# atmega16-128.net
KiCad netlist of a schematic drawn in EAGLE
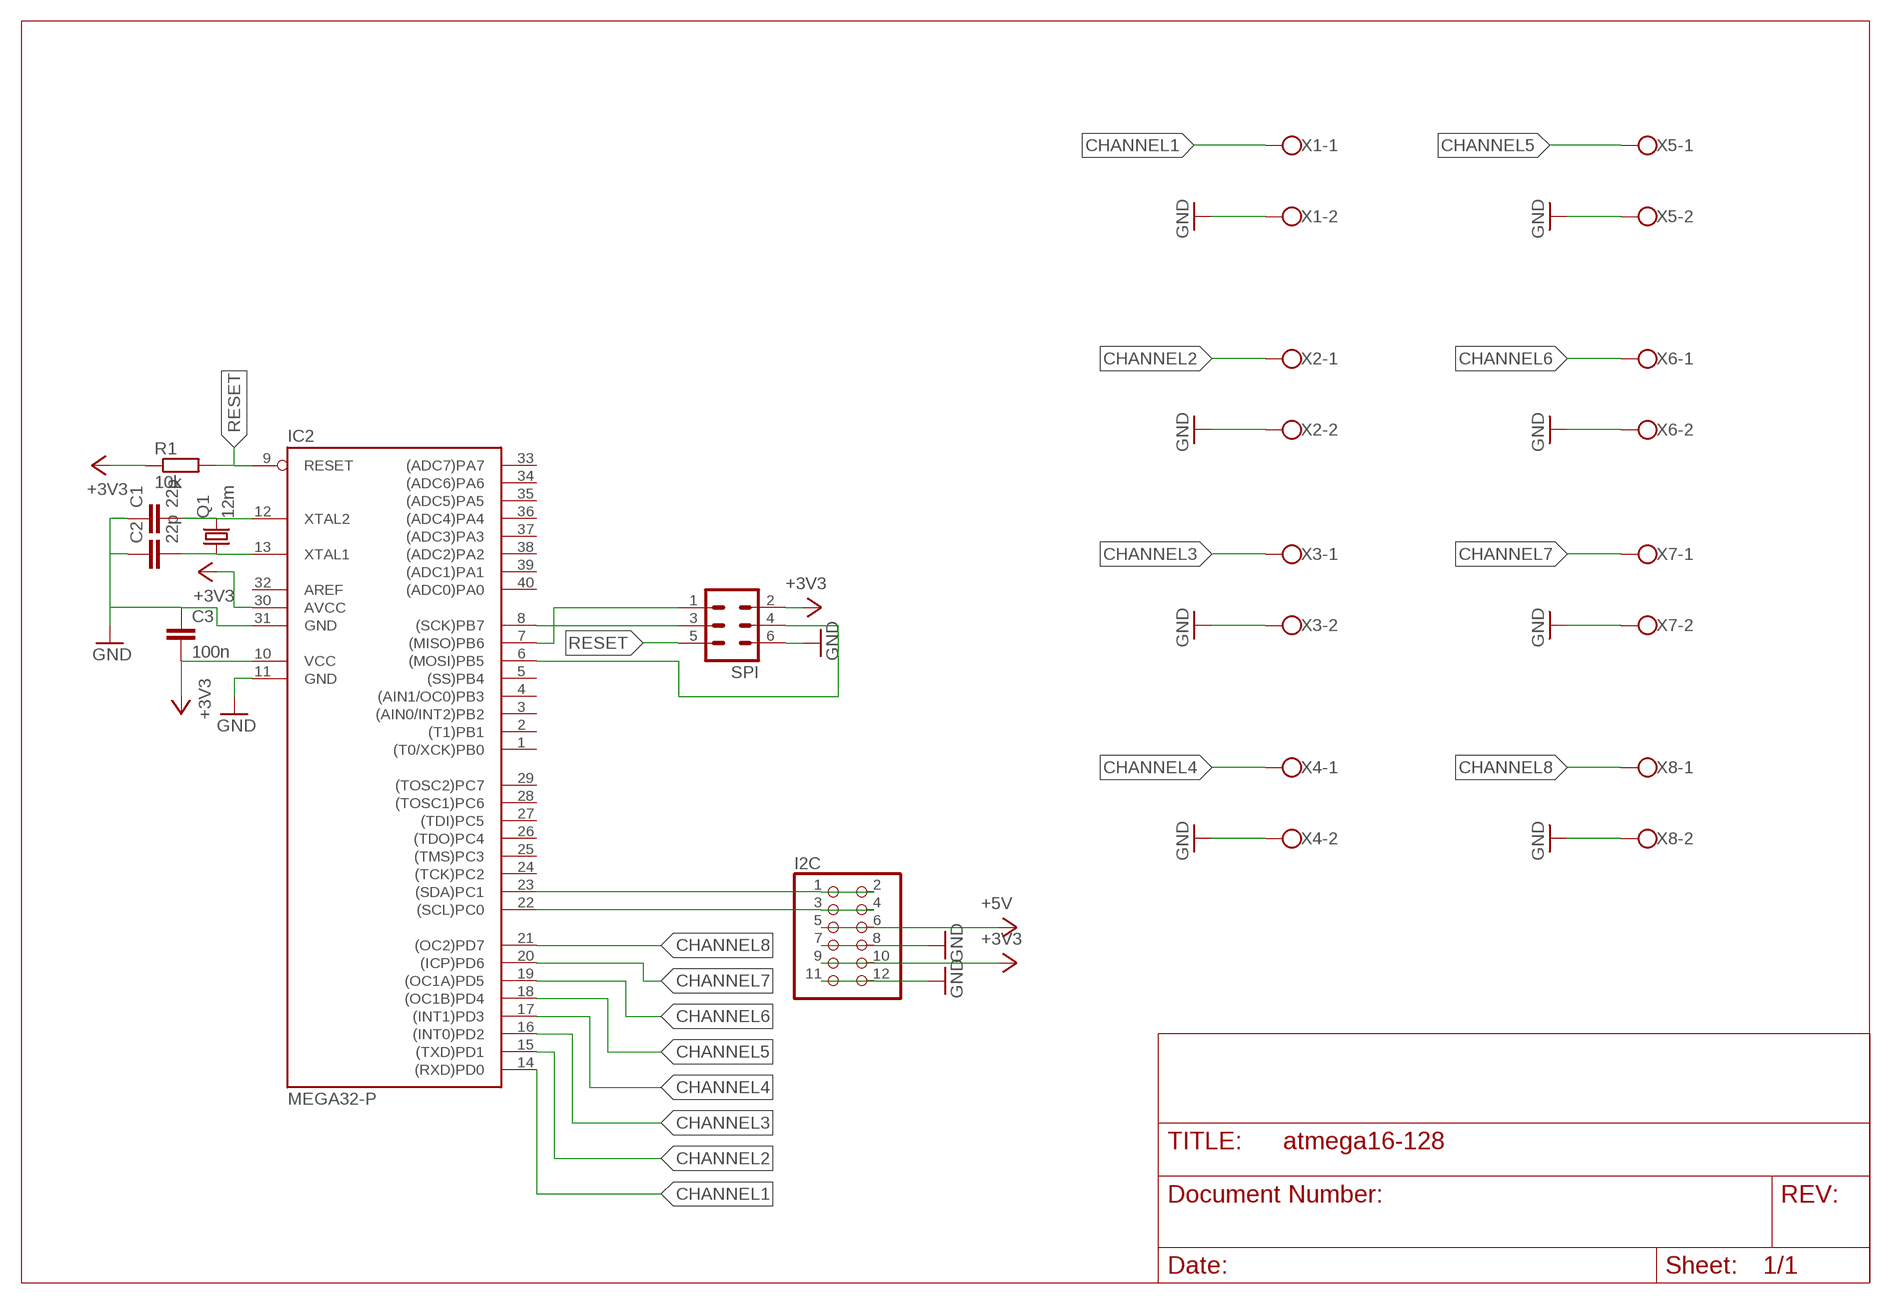
[diagram p0: schematic, sheet 1]

(export (version "E")
  (design (tool "Eeschema 10.0.6"))
  (components
    (comp (ref "C1")
      (value "22p")
      (footprint "eagle-import:C025-025X050")
      (libsource (lib "eagle-import") (part "C-EU025-025X050"))
    )
    (comp (ref "C2")
      (value "22p")
      (footprint "eagle-import:C025-025X050")
      (libsource (lib "eagle-import") (part "C-EU025-025X050"))
    )
    (comp (ref "C3")
      (value "100n")
      (footprint "eagle-import:C025-025X050")
      (libsource (lib "eagle-import") (part "C-EU025-025X050"))
    )
    (comp (ref "I2C")
      (value "PINHD-2X6")
      (footprint "eagle-import:2X06")
      (libsource (lib "eagle-import") (part "PINHD-2X6"))
    )
    (comp (ref "IC2")
      (value "MEGA32-P")
      (footprint "eagle-import:DIL40")
      (fields (field (name "MPN") "ATMEGA32-16PU"))
      (libsource (lib "eagle-import") (part "MEGA32-P"))
    )
    (comp (ref "Q1")
      (value "12m")
      (footprint "eagle-import:HC49_S")
      (libsource (lib "eagle-import") (part "CRYSTALHC49S"))
    )
    (comp (ref "R1")
      (value "10k")
      (footprint "eagle-import:0207_10")
      (libsource (lib "eagle-import") (part "R-EU_0207/10"))
    )
    (comp (ref "SPI")
      (value "ML6")
      (footprint "eagle-import:ML6")
      (libsource (lib "eagle-import") (part "ML6"))
    )
    (comp (ref "X1")
      (value "W237-102")
      (footprint "eagle-import:W237-102")
      (fields (field (name "MPN") "237-102"))
      (libsource (lib "eagle-import") (part "W237-102"))
    )
    (comp (ref "X2")
      (value "W237-102")
      (footprint "eagle-import:W237-102")
      (fields (field (name "MPN") "237-102"))
      (libsource (lib "eagle-import") (part "W237-102"))
    )
    (comp (ref "X3")
      (value "W237-102")
      (footprint "eagle-import:W237-102")
      (fields (field (name "MPN") "237-102"))
      (libsource (lib "eagle-import") (part "W237-102"))
    )
    (comp (ref "X4")
      (value "W237-102")
      (footprint "eagle-import:W237-102")
      (fields (field (name "MPN") "237-102"))
      (libsource (lib "eagle-import") (part "W237-102"))
    )
    (comp (ref "X5")
      (value "W237-102")
      (footprint "eagle-import:W237-102")
      (fields (field (name "MPN") "237-102"))
      (libsource (lib "eagle-import") (part "W237-102"))
    )
    (comp (ref "X6")
      (value "W237-102")
      (footprint "eagle-import:W237-102")
      (fields (field (name "MPN") "237-102"))
      (libsource (lib "eagle-import") (part "W237-102"))
    )
    (comp (ref "X7")
      (value "W237-102")
      (footprint "eagle-import:W237-102")
      (fields (field (name "MPN") "237-102"))
      (libsource (lib "eagle-import") (part "W237-102"))
    )
    (comp (ref "X8")
      (value "W237-102")
      (footprint "eagle-import:W237-102")
      (fields (field (name "MPN") "237-102"))
      (libsource (lib "eagle-import") (part "W237-102"))
    )
  )
  (nets
    (net (code "1") (name "+3V3") (class "Default")
      (node (ref "C3") (pin "2") (pinfunction "2_2") (pintype "passive"))
      (node (ref "I2C") (pin "10") (pinfunction "10_10") (pintype "passive"))
      (node (ref "I2C") (pin "9") (pinfunction "9_9") (pintype "passive"))
      (node (ref "IC2") (pin "10") (pinfunction "VCC_10") (pintype "power_in"))
      (node (ref "IC2") (pin "30") (pinfunction "AVCC_30") (pintype "power_in"))
      (node (ref "R1") (pin "1") (pinfunction "1_1") (pintype "passive"))
      (node (ref "SPI") (pin "2") (pinfunction "2_2") (pintype "passive"))
    )
    (net (code "2") (name "+5V") (class "Default")
      (node (ref "I2C") (pin "5") (pinfunction "5_5") (pintype "passive"))
      (node (ref "I2C") (pin "6") (pinfunction "6_6") (pintype "passive"))
    )
    (net (code "3") (name "CHANNEL1") (class "Default")
      (node (ref "IC2") (pin "14") (pinfunction "(RXD)PD0_14") (pintype "bidirectional"))
      (node (ref "X1") (pin "1") (pinfunction "KL_1") (pintype "passive"))
    )
    (net (code "4") (name "CHANNEL2") (class "Default")
      (node (ref "IC2") (pin "15") (pinfunction "(TXD)PD1_15") (pintype "bidirectional"))
      (node (ref "X2") (pin "1") (pinfunction "KL_1") (pintype "passive"))
    )
    (net (code "5") (name "CHANNEL3") (class "Default")
      (node (ref "IC2") (pin "16") (pinfunction "(INT0)PD2_16") (pintype "bidirectional"))
      (node (ref "X3") (pin "1") (pinfunction "KL_1") (pintype "passive"))
    )
    (net (code "6") (name "CHANNEL4") (class "Default")
      (node (ref "IC2") (pin "17") (pinfunction "(INT1)PD3_17") (pintype "bidirectional"))
      (node (ref "X4") (pin "1") (pinfunction "KL_1") (pintype "passive"))
    )
    (net (code "7") (name "CHANNEL5") (class "Default")
      (node (ref "IC2") (pin "18") (pinfunction "(OC1B)PD4_18") (pintype "bidirectional"))
      (node (ref "X5") (pin "1") (pinfunction "KL_1") (pintype "passive"))
    )
    (net (code "8") (name "CHANNEL6") (class "Default")
      (node (ref "IC2") (pin "19") (pinfunction "(OC1A)PD5_19") (pintype "bidirectional"))
      (node (ref "X6") (pin "1") (pinfunction "KL_1") (pintype "passive"))
    )
    (net (code "9") (name "CHANNEL7") (class "Default")
      (node (ref "IC2") (pin "20") (pinfunction "(ICP)PD6_20") (pintype "bidirectional"))
      (node (ref "X7") (pin "1") (pinfunction "KL_1") (pintype "passive"))
    )
    (net (code "10") (name "CHANNEL8") (class "Default")
      (node (ref "IC2") (pin "21") (pinfunction "(OC2)PD7_21") (pintype "bidirectional"))
      (node (ref "X8") (pin "1") (pinfunction "KL_1") (pintype "passive"))
    )
    (net (code "11") (name "GND") (class "Default")
      (node (ref "C1") (pin "1") (pinfunction "1_1") (pintype "passive"))
      (node (ref "C2") (pin "1") (pinfunction "1_1") (pintype "passive"))
      (node (ref "C3") (pin "1") (pinfunction "1_1") (pintype "passive"))
      (node (ref "I2C") (pin "11") (pinfunction "11_11") (pintype "passive"))
      (node (ref "I2C") (pin "12") (pinfunction "12_12") (pintype "passive"))
      (node (ref "I2C") (pin "7") (pinfunction "7_7") (pintype "passive"))
      (node (ref "I2C") (pin "8") (pinfunction "8_8") (pintype "passive"))
      (node (ref "IC2") (pin "11") (pinfunction "GND_11") (pintype "power_in"))
      (node (ref "IC2") (pin "31") (pinfunction "GND_31") (pintype "power_in"))
      (node (ref "SPI") (pin "6") (pinfunction "6_6") (pintype "passive"))
      (node (ref "X1") (pin "2") (pinfunction "KL_2") (pintype "passive"))
      (node (ref "X2") (pin "2") (pinfunction "KL_2") (pintype "passive"))
      (node (ref "X3") (pin "2") (pinfunction "KL_2") (pintype "passive"))
      (node (ref "X4") (pin "2") (pinfunction "KL_2") (pintype "passive"))
      (node (ref "X5") (pin "2") (pinfunction "KL_2") (pintype "passive"))
      (node (ref "X6") (pin "2") (pinfunction "KL_2") (pintype "passive"))
      (node (ref "X7") (pin "2") (pinfunction "KL_2") (pintype "passive"))
      (node (ref "X8") (pin "2") (pinfunction "KL_2") (pintype "passive"))
    )
    (net (code "12") (name "Net-(IC2-(MISO)PB6)") (class "Default")
      (node (ref "IC2") (pin "7") (pinfunction "(MISO)PB6_7") (pintype "bidirectional"))
      (node (ref "SPI") (pin "1") (pinfunction "1_1") (pintype "passive"))
    )
    (net (code "13") (name "Net-(IC2-(MOSI)PB5)") (class "Default")
      (node (ref "IC2") (pin "6") (pinfunction "(MOSI)PB5_6") (pintype "bidirectional"))
      (node (ref "SPI") (pin "4") (pinfunction "4_4") (pintype "passive"))
    )
    (net (code "14") (name "Net-(IC2-(SCK)PB7)") (class "Default")
      (node (ref "IC2") (pin "8") (pinfunction "(SCK)PB7_8") (pintype "bidirectional"))
      (node (ref "SPI") (pin "3") (pinfunction "3_3") (pintype "passive"))
    )
    (net (code "15") (name "Net-(IC2-(SCL)PC0)") (class "Default")
      (node (ref "I2C") (pin "3") (pinfunction "3_3") (pintype "passive"))
      (node (ref "I2C") (pin "4") (pinfunction "4_4") (pintype "passive"))
      (node (ref "IC2") (pin "22") (pinfunction "(SCL)PC0_22") (pintype "bidirectional"))
    )
    (net (code "16") (name "Net-(IC2-(SDA)PC1)") (class "Default")
      (node (ref "I2C") (pin "1") (pinfunction "1_1") (pintype "passive"))
      (node (ref "I2C") (pin "2") (pinfunction "2_2") (pintype "passive"))
      (node (ref "IC2") (pin "23") (pinfunction "(SDA)PC1_23") (pintype "bidirectional"))
    )
    (net (code "17") (name "Net-(IC2-XTAL1)") (class "Default")
      (node (ref "C2") (pin "2") (pinfunction "2_2") (pintype "passive"))
      (node (ref "IC2") (pin "13") (pinfunction "XTAL1_13") (pintype "bidirectional"))
      (node (ref "Q1") (pin "1") (pinfunction "1_1") (pintype "passive"))
    )
    (net (code "18") (name "Net-(IC2-XTAL2)") (class "Default")
      (node (ref "C1") (pin "2") (pinfunction "2_2") (pintype "passive"))
      (node (ref "IC2") (pin "12") (pinfunction "XTAL2_12") (pintype "bidirectional"))
      (node (ref "Q1") (pin "2") (pinfunction "2_2") (pintype "passive"))
    )
    (net (code "19") (name "RESET") (class "Default")
      (node (ref "IC2") (pin "9") (pinfunction "RESET_9") (pintype "input"))
      (node (ref "R1") (pin "2") (pinfunction "2_2") (pintype "passive"))
      (node (ref "SPI") (pin "5") (pinfunction "5_5") (pintype "passive"))
    )
    (net (code "20") (name "unconnected-(IC2-(ADC0)PA0-Pad40)") (class "Default")
      (node (ref "IC2") (pin "40") (pinfunction "(ADC0)PA0_40") (pintype "bidirectional"))
    )
    (net (code "21") (name "unconnected-(IC2-(ADC1)PA1-Pad39)") (class "Default")
      (node (ref "IC2") (pin "39") (pinfunction "(ADC1)PA1_39") (pintype "bidirectional"))
    )
    (net (code "22") (name "unconnected-(IC2-(ADC2)PA2-Pad38)") (class "Default")
      (node (ref "IC2") (pin "38") (pinfunction "(ADC2)PA2_38") (pintype "bidirectional"))
    )
    (net (code "23") (name "unconnected-(IC2-(ADC3)PA3-Pad37)") (class "Default")
      (node (ref "IC2") (pin "37") (pinfunction "(ADC3)PA3_37") (pintype "bidirectional"))
    )
    (net (code "24") (name "unconnected-(IC2-(ADC4)PA4-Pad36)") (class "Default")
      (node (ref "IC2") (pin "36") (pinfunction "(ADC4)PA4_36") (pintype "bidirectional"))
    )
    (net (code "25") (name "unconnected-(IC2-(ADC5)PA5-Pad35)") (class "Default")
      (node (ref "IC2") (pin "35") (pinfunction "(ADC5)PA5_35") (pintype "bidirectional"))
    )
    (net (code "26") (name "unconnected-(IC2-(ADC6)PA6-Pad34)") (class "Default")
      (node (ref "IC2") (pin "34") (pinfunction "(ADC6)PA6_34") (pintype "bidirectional"))
    )
    (net (code "27") (name "unconnected-(IC2-(ADC7)PA7-Pad33)") (class "Default")
      (node (ref "IC2") (pin "33") (pinfunction "(ADC7)PA7_33") (pintype "bidirectional"))
    )
    (net (code "28") (name "unconnected-(IC2-(AIN0{slash}INT2)PB2-Pad3)") (class "Default")
      (node (ref "IC2") (pin "3") (pinfunction "(AIN0/INT2)PB2_3") (pintype "bidirectional"))
    )
    (net (code "29") (name "unconnected-(IC2-(AIN1{slash}OC0)PB3-Pad4)") (class "Default")
      (node (ref "IC2") (pin "4") (pinfunction "(AIN1/OC0)PB3_4") (pintype "bidirectional"))
    )
    (net (code "30") (name "unconnected-(IC2-(SS)PB4-Pad5)") (class "Default")
      (node (ref "IC2") (pin "5") (pinfunction "(SS)PB4_5") (pintype "bidirectional"))
    )
    (net (code "31") (name "unconnected-(IC2-(T0{slash}XCK)PB0-Pad1)") (class "Default")
      (node (ref "IC2") (pin "1") (pinfunction "(T0/XCK)PB0_1") (pintype "bidirectional"))
    )
    (net (code "32") (name "unconnected-(IC2-(T1)PB1-Pad2)") (class "Default")
      (node (ref "IC2") (pin "2") (pinfunction "(T1)PB1_2") (pintype "bidirectional"))
    )
    (net (code "33") (name "unconnected-(IC2-(TCK)PC2-Pad24)") (class "Default")
      (node (ref "IC2") (pin "24") (pinfunction "(TCK)PC2_24") (pintype "bidirectional"))
    )
    (net (code "34") (name "unconnected-(IC2-(TDI)PC5-Pad27)") (class "Default")
      (node (ref "IC2") (pin "27") (pinfunction "(TDI)PC5_27") (pintype "bidirectional"))
    )
    (net (code "35") (name "unconnected-(IC2-(TDO)PC4-Pad26)") (class "Default")
      (node (ref "IC2") (pin "26") (pinfunction "(TDO)PC4_26") (pintype "bidirectional"))
    )
    (net (code "36") (name "unconnected-(IC2-(TMS)PC3-Pad25)") (class "Default")
      (node (ref "IC2") (pin "25") (pinfunction "(TMS)PC3_25") (pintype "bidirectional"))
    )
    (net (code "37") (name "unconnected-(IC2-(TOSC1)PC6-Pad28)") (class "Default")
      (node (ref "IC2") (pin "28") (pinfunction "(TOSC1)PC6_28") (pintype "bidirectional"))
    )
    (net (code "38") (name "unconnected-(IC2-(TOSC2)PC7-Pad29)") (class "Default")
      (node (ref "IC2") (pin "29") (pinfunction "(TOSC2)PC7_29") (pintype "bidirectional"))
    )
    (net (code "39") (name "unconnected-(IC2-AREF-Pad32)") (class "Default")
      (node (ref "IC2") (pin "32") (pinfunction "AREF_32") (pintype "passive"))
    )
  )
)
